# input-shield_for_Adafruit_HUZZAH32_ESP32.net
KiCad netlist of a schematic drawn in EAGLE
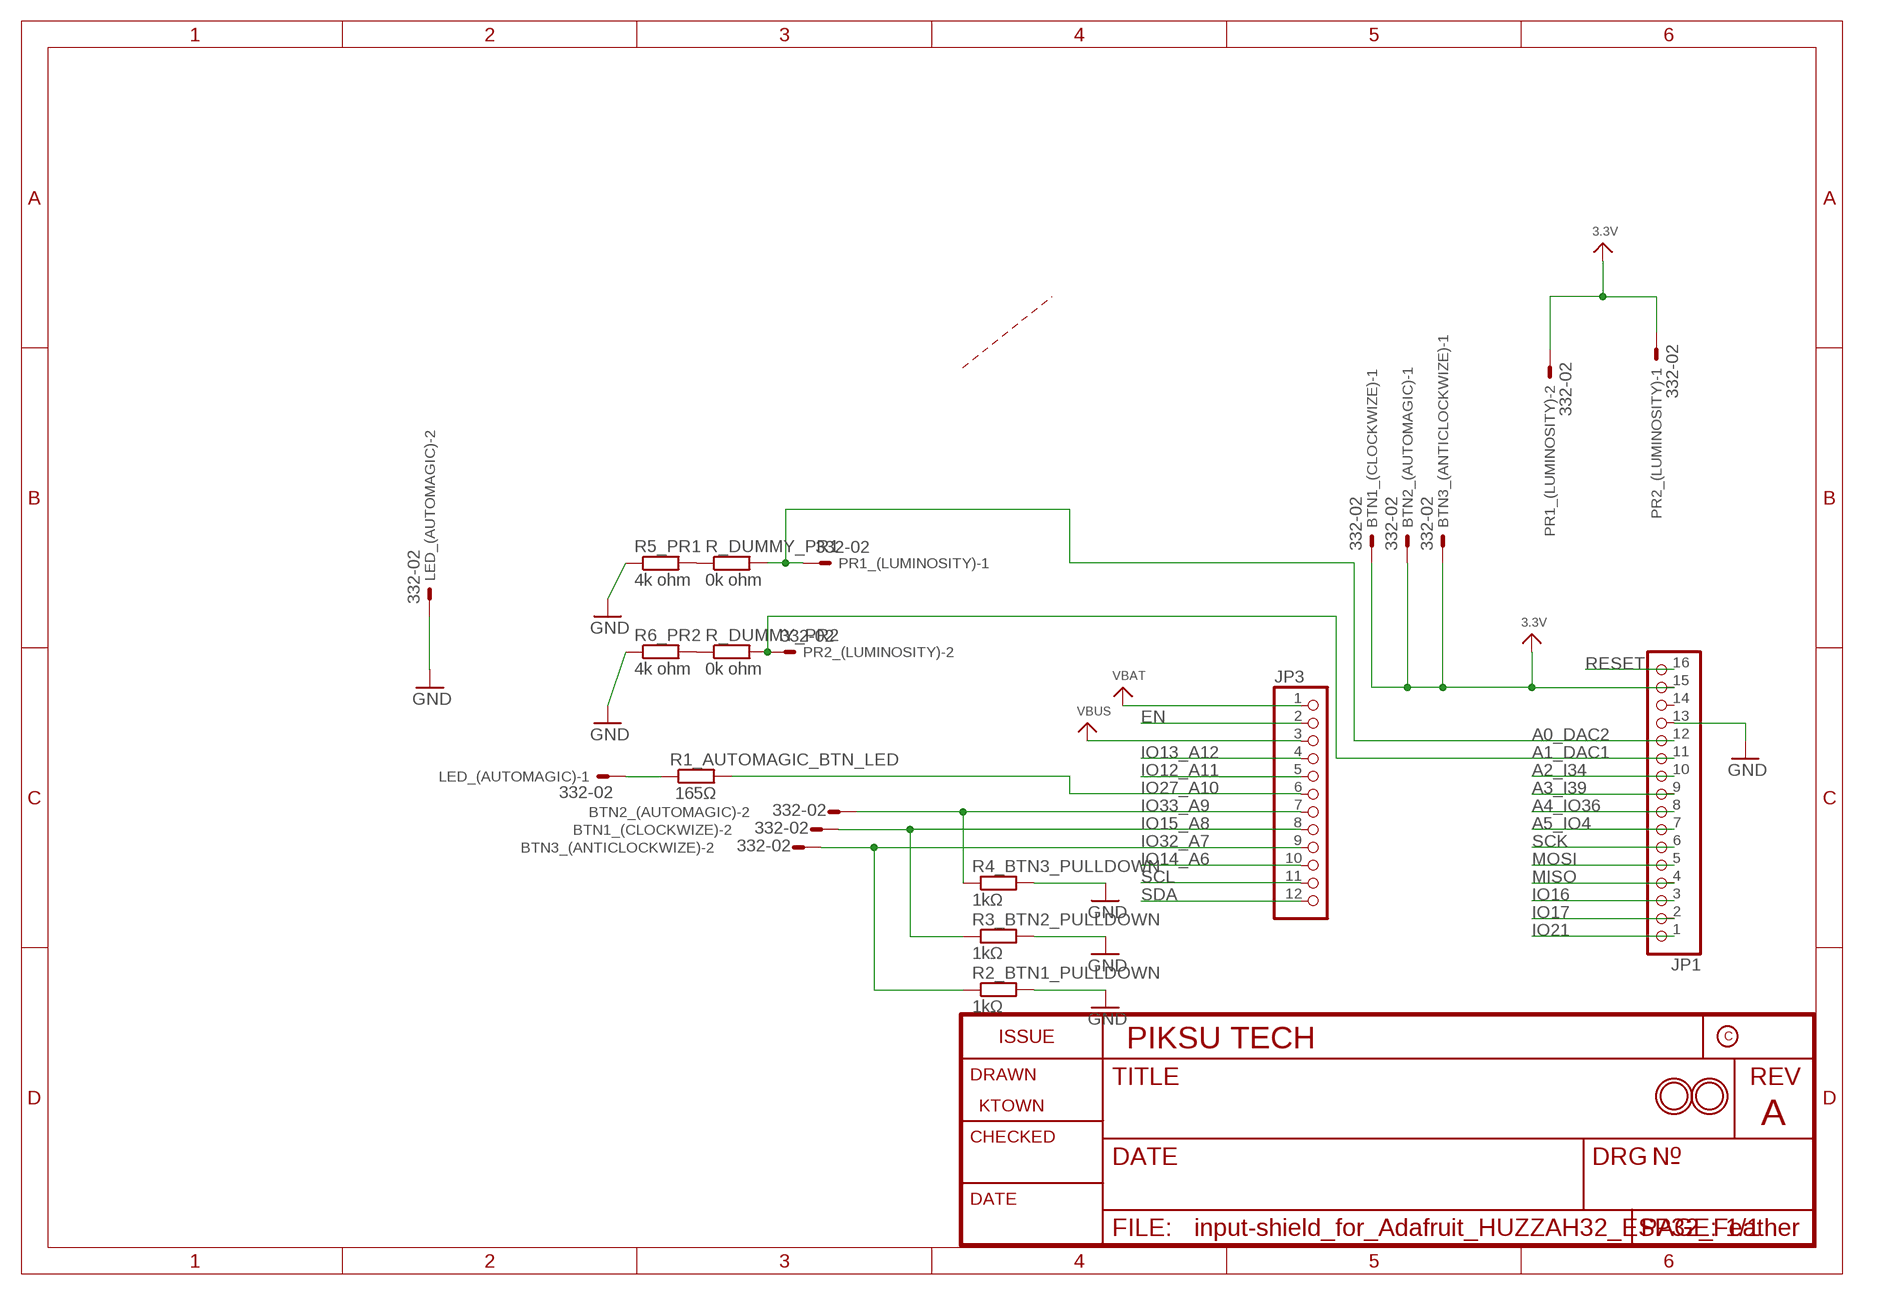
[diagram p0: schematic, sheet 1]

(export (version "E")
  (design (tool "Eeschema 10.0.6"))
  (components
    (comp (ref "BTN1_(CLOCKWIZE)")
      (value "332-02")
      (footprint "eagle-import:332-02")
      (libsource (lib "eagle-import") (part "332-02"))
    )
    (comp (ref "BTN2_(AUTOMAGIC)")
      (value "332-02")
      (footprint "eagle-import:332-02")
      (libsource (lib "eagle-import") (part "332-02"))
    )
    (comp (ref "BTN3_(ANTICLOCKWIZE)")
      (value "332-02")
      (footprint "eagle-import:332-02")
      (libsource (lib "eagle-import") (part "332-02"))
    )
    (comp (ref "JP1")
      (value "HEADER-1X16_MIN")
      (footprint "eagle-import:1X16_ROUND_MIN")
      (libsource (lib "eagle-import") (part "HEADER-1X16_MIN"))
    )
    (comp (ref "JP3")
      (value "HEADER-1X12_MIN")
      (footprint "eagle-import:1X12_ROUND_MIN")
      (libsource (lib "eagle-import") (part "HEADER-1X12_MIN"))
    )
    (comp (ref "LED_(AUTOMAGIC)")
      (value "332-02")
      (footprint "eagle-import:332-02")
      (libsource (lib "eagle-import") (part "332-02"))
    )
    (comp (ref "PR1_(LUMINOSITY)")
      (value "332-02")
      (footprint "eagle-import:332-02")
      (libsource (lib "eagle-import") (part "332-02"))
    )
    (comp (ref "PR2_(LUMINOSITY)")
      (value "332-02")
      (footprint "eagle-import:332-02")
      (libsource (lib "eagle-import") (part "332-02"))
    )
    (comp (ref "R1_AUTOMAGIC_BTN_LED")
      (value "165Ω")
      (footprint "eagle-import:0204_7")
      (libsource (lib "eagle-import") (part "R-EU_0204/7"))
    )
    (comp (ref "R2_BTN1_PULLDOWN")
      (value "1kΩ")
      (footprint "eagle-import:0204_7")
      (libsource (lib "eagle-import") (part "R-EU_0204/7"))
    )
    (comp (ref "R3_BTN2_PULLDOWN")
      (value "1kΩ")
      (footprint "eagle-import:0204_7")
      (libsource (lib "eagle-import") (part "R-EU_0204/7"))
    )
    (comp (ref "R4_BTN3_PULLDOWN")
      (value "1kΩ")
      (footprint "eagle-import:0204_7")
      (libsource (lib "eagle-import") (part "R-EU_0204/7"))
    )
    (comp (ref "R5_PR1")
      (value "4k ohm")
      (footprint "eagle-import:0204_7")
      (libsource (lib "eagle-import") (part "R-EU_0204/7"))
    )
    (comp (ref "R6_PR2")
      (value "4k ohm")
      (footprint "eagle-import:0204_7")
      (libsource (lib "eagle-import") (part "R-EU_0204/7"))
    )
    (comp (ref "R_DUMMY_PR1")
      (value "0k ohm")
      (footprint "eagle-import:0204_7")
      (libsource (lib "eagle-import") (part "R-EU_0204/7"))
    )
    (comp (ref "R_DUMMY_PR2")
      (value "0k ohm")
      (footprint "eagle-import:0204_7")
      (libsource (lib "eagle-import") (part "R-EU_0204/7"))
    )
    (comp (ref "U$31")
      (value "MOUNTINGHOLE2.5")
      (footprint "eagle-import:MOUNTINGHOLE_2.5_PLATED")
      (libsource (lib "eagle-import") (part "MOUNTINGHOLE2.5"))
    )
    (comp (ref "U$32")
      (value "MOUNTINGHOLE2.5")
      (footprint "eagle-import:MOUNTINGHOLE_2.5_PLATED")
      (libsource (lib "eagle-import") (part "MOUNTINGHOLE2.5"))
    )
  )
  (nets
    (net (code "1") (name "/A0_DAC2") (class "Default")
      (node (ref "JP1") (pin "12") (pinfunction "12_12") (pintype "passive"))
      (node (ref "PR1_(LUMINOSITY)") (pin "1") (pinfunction "S_1") (pintype "passive"))
      (node (ref "R_DUMMY_PR1") (pin "2") (pinfunction "2_2") (pintype "passive"))
    )
    (net (code "2") (name "/A1_DAC1") (class "Default")
      (node (ref "JP1") (pin "11") (pinfunction "11_11") (pintype "passive"))
      (node (ref "PR2_(LUMINOSITY)") (pin "2") (pinfunction "S_2") (pintype "passive"))
      (node (ref "R_DUMMY_PR2") (pin "2") (pinfunction "2_2") (pintype "passive"))
    )
    (net (code "3") (name "/A2_I34") (class "Default")
      (node (ref "JP1") (pin "10") (pinfunction "10_10") (pintype "passive"))
    )
    (net (code "4") (name "/A3_I39") (class "Default")
      (node (ref "JP1") (pin "9") (pinfunction "9_9") (pintype "passive"))
    )
    (net (code "5") (name "/A4_IO36") (class "Default")
      (node (ref "JP1") (pin "8") (pinfunction "8_8") (pintype "passive"))
    )
    (net (code "6") (name "/A5_IO4") (class "Default")
      (node (ref "JP1") (pin "7") (pinfunction "7_7") (pintype "passive"))
    )
    (net (code "7") (name "/EN") (class "Default")
      (node (ref "JP3") (pin "2") (pinfunction "2_2") (pintype "passive"))
    )
    (net (code "8") (name "/IO12_A11") (class "Default")
      (node (ref "JP3") (pin "5") (pinfunction "5_5") (pintype "passive"))
    )
    (net (code "9") (name "/IO13_A12") (class "Default")
      (node (ref "JP3") (pin "4") (pinfunction "4_4") (pintype "passive"))
    )
    (net (code "10") (name "/IO14_A6") (class "Default")
      (node (ref "JP3") (pin "10") (pinfunction "10_10") (pintype "passive"))
    )
    (net (code "11") (name "/IO15_A8") (class "Default")
      (node (ref "BTN1_(CLOCKWIZE)") (pin "2") (pinfunction "S_2") (pintype "passive"))
      (node (ref "JP3") (pin "8") (pinfunction "8_8") (pintype "passive"))
      (node (ref "R3_BTN2_PULLDOWN") (pin "1") (pinfunction "1_1") (pintype "passive"))
    )
    (net (code "12") (name "/IO16") (class "Default")
      (node (ref "JP1") (pin "3") (pinfunction "3_3") (pintype "passive"))
    )
    (net (code "13") (name "/IO17") (class "Default")
      (node (ref "JP1") (pin "2") (pinfunction "2_2") (pintype "passive"))
    )
    (net (code "14") (name "/IO21") (class "Default")
      (node (ref "JP1") (pin "1") (pinfunction "1_1") (pintype "passive"))
    )
    (net (code "15") (name "/IO27_A10") (class "Default")
      (node (ref "JP3") (pin "6") (pinfunction "6_6") (pintype "passive"))
      (node (ref "R1_AUTOMAGIC_BTN_LED") (pin "2") (pinfunction "2_2") (pintype "passive"))
    )
    (net (code "16") (name "/IO32_A7") (class "Default")
      (node (ref "BTN3_(ANTICLOCKWIZE)") (pin "2") (pinfunction "S_2") (pintype "passive"))
      (node (ref "JP3") (pin "9") (pinfunction "9_9") (pintype "passive"))
      (node (ref "R2_BTN1_PULLDOWN") (pin "1") (pinfunction "1_1") (pintype "passive"))
    )
    (net (code "17") (name "/IO33_A9") (class "Default")
      (node (ref "BTN2_(AUTOMAGIC)") (pin "2") (pinfunction "S_2") (pintype "passive"))
      (node (ref "JP3") (pin "7") (pinfunction "7_7") (pintype "passive"))
      (node (ref "R4_BTN3_PULLDOWN") (pin "1") (pinfunction "1_1") (pintype "passive"))
    )
    (net (code "18") (name "/MISO") (class "Default")
      (node (ref "JP1") (pin "4") (pinfunction "4_4") (pintype "passive"))
    )
    (net (code "19") (name "/MOSI") (class "Default")
      (node (ref "JP1") (pin "5") (pinfunction "5_5") (pintype "passive"))
    )
    (net (code "20") (name "/RESET") (class "Default")
      (node (ref "JP1") (pin "16") (pinfunction "16_16") (pintype "passive"))
    )
    (net (code "21") (name "/SCK") (class "Default")
      (node (ref "JP1") (pin "6") (pinfunction "6_6") (pintype "passive"))
    )
    (net (code "22") (name "/SCL") (class "Default")
      (node (ref "JP3") (pin "11") (pinfunction "11_11") (pintype "passive"))
    )
    (net (code "23") (name "/SDA") (class "Default")
      (node (ref "JP3") (pin "12") (pinfunction "12_12") (pintype "passive"))
    )
    (net (code "24") (name "3.3V") (class "Default")
      (node (ref "BTN1_(CLOCKWIZE)") (pin "1") (pinfunction "S_1") (pintype "passive"))
      (node (ref "BTN2_(AUTOMAGIC)") (pin "1") (pinfunction "S_1") (pintype "passive"))
      (node (ref "BTN3_(ANTICLOCKWIZE)") (pin "1") (pinfunction "S_1") (pintype "passive"))
      (node (ref "JP1") (pin "15") (pinfunction "15_15") (pintype "passive"))
      (node (ref "PR1_(LUMINOSITY)") (pin "2") (pinfunction "S_2") (pintype "passive"))
      (node (ref "PR2_(LUMINOSITY)") (pin "1") (pinfunction "S_1") (pintype "passive"))
    )
    (net (code "25") (name "GND") (class "Default")
      (node (ref "JP1") (pin "13") (pinfunction "13_13") (pintype "passive"))
      (node (ref "LED_(AUTOMAGIC)") (pin "2") (pinfunction "S_2") (pintype "passive"))
      (node (ref "R2_BTN1_PULLDOWN") (pin "2") (pinfunction "2_2") (pintype "passive"))
      (node (ref "R3_BTN2_PULLDOWN") (pin "2") (pinfunction "2_2") (pintype "passive"))
      (node (ref "R4_BTN3_PULLDOWN") (pin "2") (pinfunction "2_2") (pintype "passive"))
      (node (ref "R5_PR1") (pin "1") (pinfunction "1_1") (pintype "passive"))
      (node (ref "R6_PR2") (pin "1") (pinfunction "1_1") (pintype "passive"))
    )
    (net (code "26") (name "Net-(LED_(AUTOMAGIC)A-S)") (class "Default")
      (node (ref "LED_(AUTOMAGIC)") (pin "1") (pinfunction "S_1") (pintype "passive"))
      (node (ref "R1_AUTOMAGIC_BTN_LED") (pin "1") (pinfunction "1_1") (pintype "passive"))
    )
    (net (code "27") (name "Net-(R5_PR1-Pad2)") (class "Default")
      (node (ref "R5_PR1") (pin "2") (pinfunction "2_2") (pintype "passive"))
      (node (ref "R_DUMMY_PR1") (pin "1") (pinfunction "1_1") (pintype "passive"))
    )
    (net (code "28") (name "Net-(R6_PR2-Pad2)") (class "Default")
      (node (ref "R6_PR2") (pin "2") (pinfunction "2_2") (pintype "passive"))
      (node (ref "R_DUMMY_PR2") (pin "1") (pinfunction "1_1") (pintype "passive"))
    )
    (net (code "29") (name "VBAT") (class "Default")
      (node (ref "JP3") (pin "1") (pinfunction "1_1") (pintype "passive"))
    )
    (net (code "30") (name "VBUS") (class "Default")
      (node (ref "JP3") (pin "3") (pinfunction "3_3") (pintype "passive"))
    )
    (net (code "31") (name "unconnected-(JP1-Pad14)") (class "Default")
      (node (ref "JP1") (pin "14") (pinfunction "14_14") (pintype "passive"))
    )
  )
)
